# MAIN.net
KiCad netlist of a schematic drawn in Altium Designer
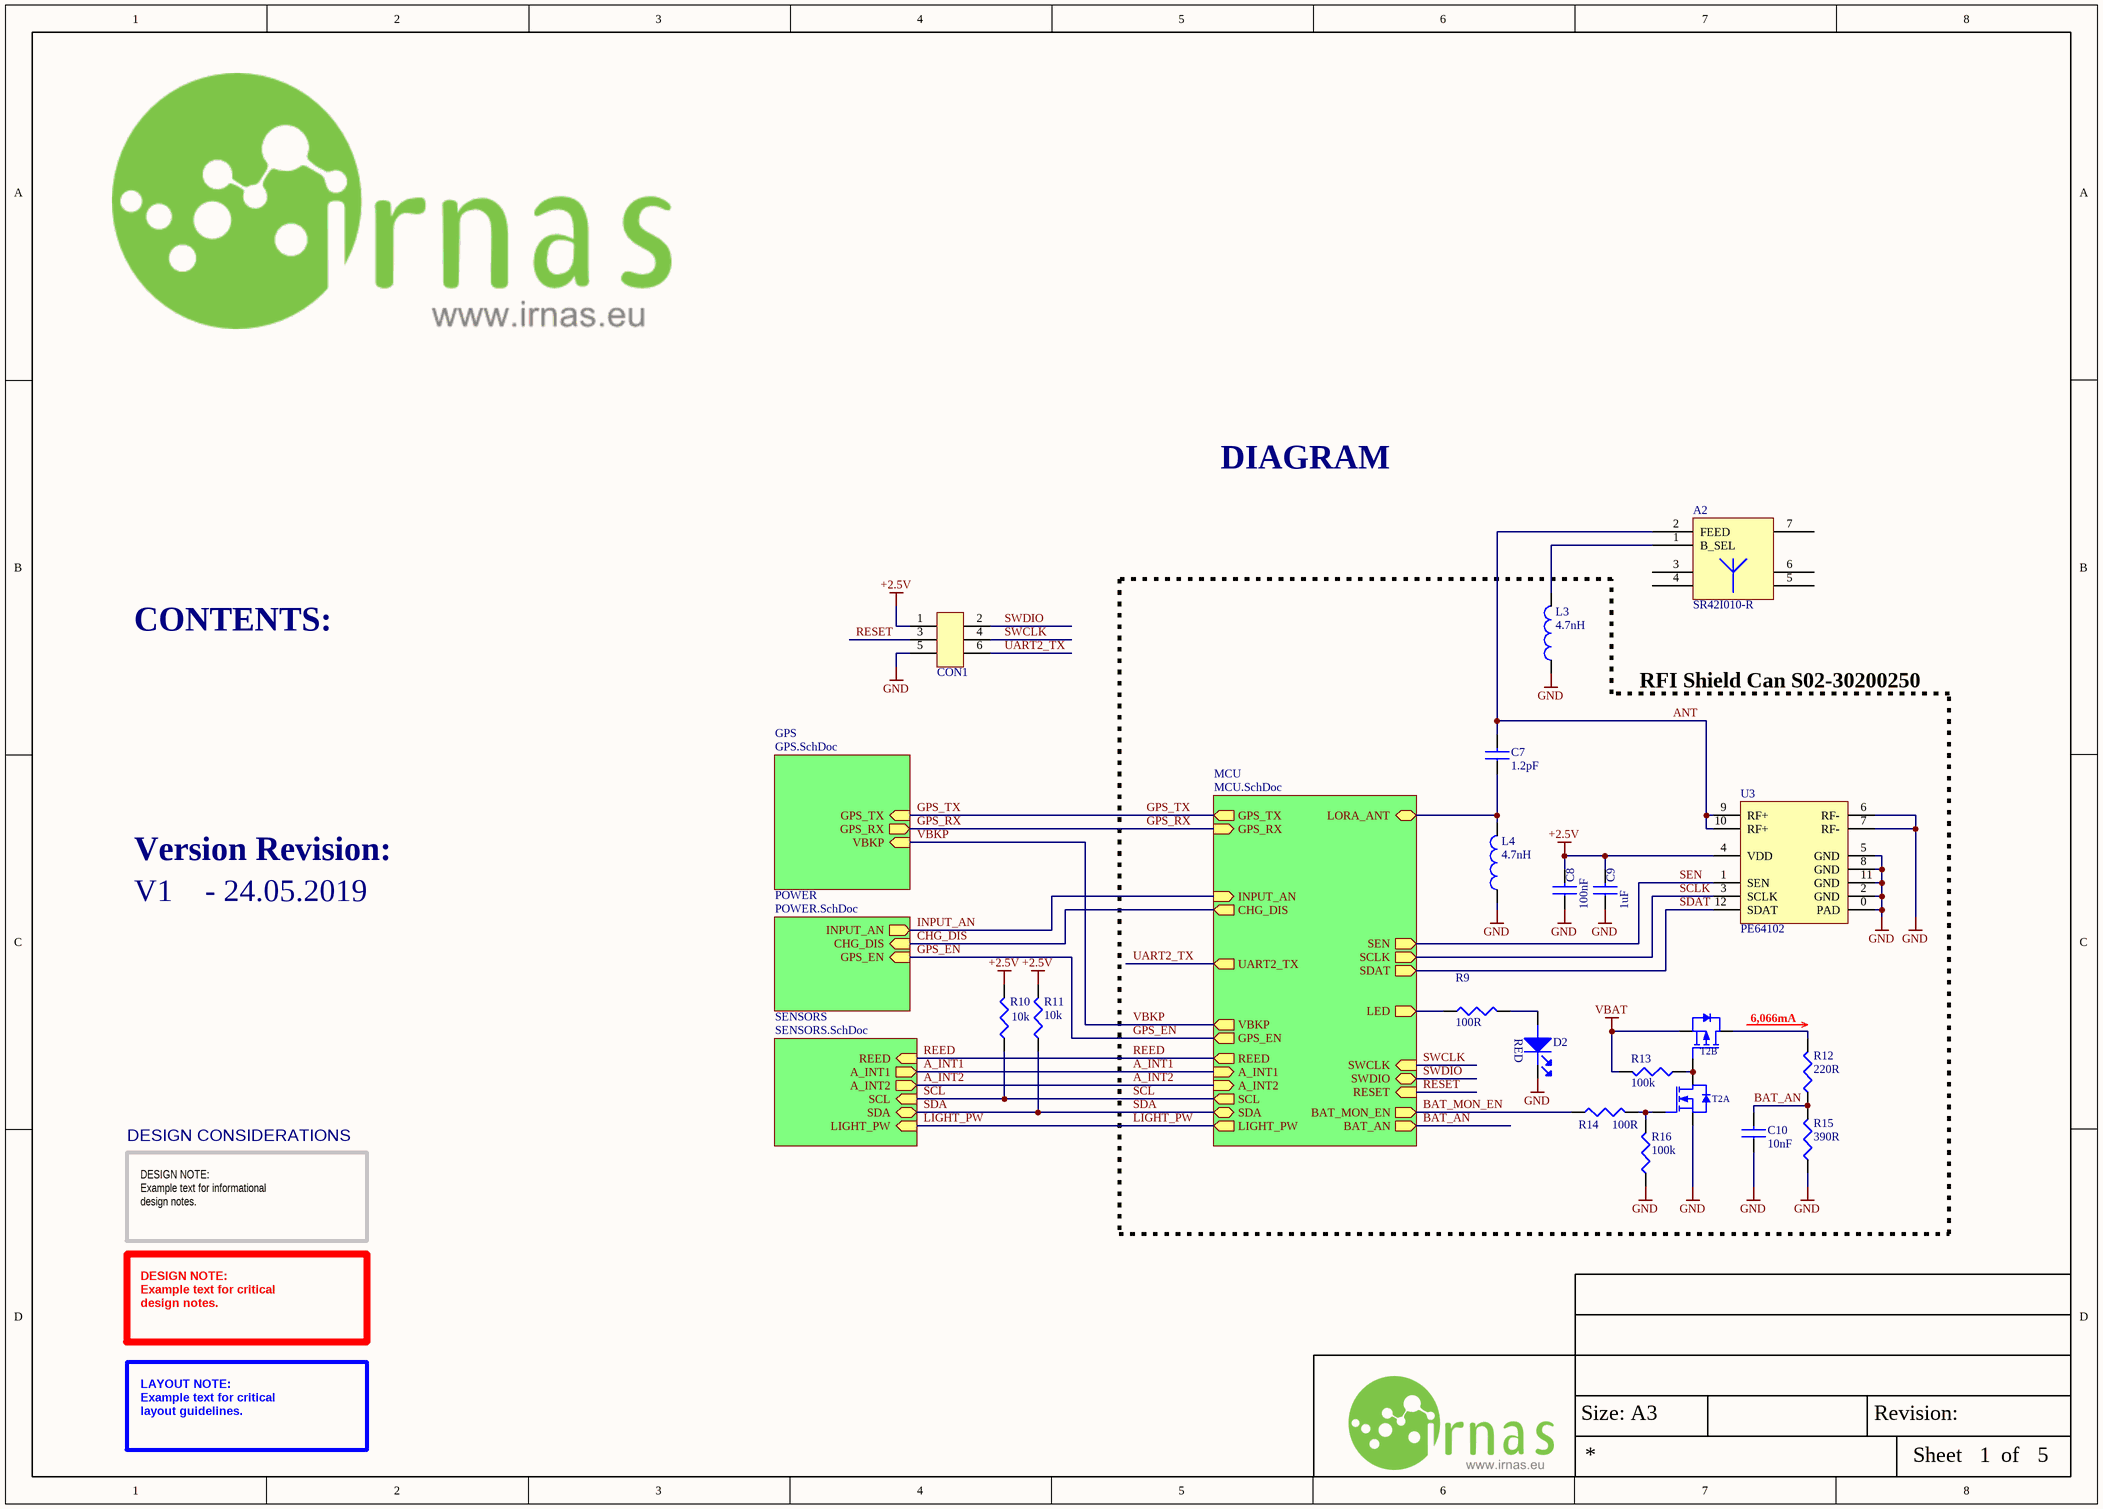
[diagram p0: MAIN.SchDoc]

(export (version "E")
  (design (tool "Eeschema 10.0.6"))
  (components
    (comp (ref "A2")
      (value "SR42I010-R")
      (footprint "LORA_PCB_ANTENNA")
      (description "Antenna SMD -4dBi Gain 870MHz/928MHz Automotive 7-Pin SMD T/R")
      (fields (field (name "MANUFACTURER") "Antenova"))
      (libsource (lib "Passive") (part "ANT - SR42I010-R_1"))
    )
    (comp (ref "C7")
      (value "1.2pF")
      (footprint "CAP0402")
      (description "CAP CER 4700PF 50V X7R 0402")
      (fields
        (field (name "MANUFACTURER") "KEMET")
        (field (name "MANUFACTURER PART NUMBER") "C0402C472K5RAC-TU")
      )
      (libsource (lib "Passive") (part "C - 4.7nF/0402"))
    )
    (comp (ref "C8")
      (value "100nF")
      (footprint "CAP0402")
      (fields
        (field (name "MANUFACTURER") "Multicomp")
        (field (name "MANUFACTURER PART NUMBER") "MC0402X104J160CT")
        (field (name "TOLERANCE") "5%")
      )
      (libsource (lib "Passive") (part "C - 100nF/0402"))
    )
    (comp (ref "C9")
      (value "1uF")
      (footprint "CAP0402")
      (description "CAP CER 1UF 10V 20% X5R 0402")
      (fields
        (field (name "MANUFACTURER") "Murata")
        (field (name "MANUFACTURER PART NUMBER") "GRM155R61A105ME15D")
      )
      (libsource (lib "Passive") (part "C - 1uF/0402"))
    )
    (comp (ref "C10")
      (value "10nF")
      (footprint "CAP0402")
      (description "CAP CER 10000PF 16V X7R 0402")
      (fields
        (field (name "MANUFACTURER") "Murata")
        (field (name "MANUFACTURER PART NUMBER") "GRM155R71C103KA01D")
      )
      (libsource (lib "Passive") (part "C - 10nF/0402"))
    )
    (comp (ref "CON1")
      (value "Tag connect")
      (footprint "TC2030-IDC-NL")
      (libsource (lib "Connectors") (part "tag connecot 6 pin"))
    )
    (comp (ref "D2")
      (value "LED RED")
      (footprint "LED0603")
      (description "BROADCOM LIMITED - HSMS-C190 - LED, RED, 10MCD, 626NM")
      (fields
        (field (name "MANUFACTURER") "BROADCOM LIMITED")
        (field (name "MANUFACTURER PART NUMBER") "HSMS-C190")
      )
      (libsource (lib "Active") (part "LED - LED RED"))
    )
    (comp (ref "L3")
      (value "4.7nH")
      (footprint "IND0402")
      (description "Inductor RF Chip Multi-Layer 4.3nH 0.3nH 100MHz 8Q-Factor Air 300mA 210mOhm DCR 0402 Paper T/R")
      (fields
        (field (name "MANUFACTURER") "Murata")
        (field (name "MANUFACTURER PART NUMBER") "LQG15HN4N3S02D")
      )
      (libsource (lib "Passive") (part "L - 4.3nH/0402"))
    )
    (comp (ref "L4")
      (value "4.7nH")
      (footprint "IND0402")
      (description "Inductor RF Chip Multi-Layer 4.3nH 0.3nH 100MHz 8Q-Factor Air 300mA 210mOhm DCR 0402 Paper T/R")
      (fields
        (field (name "MANUFACTURER") "Murata")
        (field (name "MANUFACTURER PART NUMBER") "LQG15HN4N3S02D")
      )
      (libsource (lib "Passive") (part "L - 4.3nH/0402"))
    )
    (comp (ref "R9")
      (value "100R")
      (footprint "RES0402")
      (fields
        (field (name "MANUFACTURER") "Multicomp")
        (field (name "MANUFACTURER PART NUMBER") "MCMR04X1000FTL")
        (field (name "TOLERANCE") "1%")
      )
      (libsource (lib "Passive") (part "R - 100R/0402"))
    )
    (comp (ref "R10")
      (value "10k")
      (footprint "RES0402")
      (fields
        (field (name "MANUFACTURER") "Multicomp")
        (field (name "MANUFACTURER PART NUMBER") "MCWR04X1002FTL")
        (field (name "TOLERANCE") "1%")
      )
      (libsource (lib "Passive") (part "R - 10k/0402"))
    )
    (comp (ref "R11")
      (value "10k")
      (footprint "RES0402")
      (fields
        (field (name "MANUFACTURER") "Multicomp")
        (field (name "MANUFACTURER PART NUMBER") "MCWR04X1002FTL")
        (field (name "TOLERANCE") "1%")
      )
      (libsource (lib "Passive") (part "R - 10k/0402"))
    )
    (comp (ref "R12")
      (value "220R")
      (footprint "RES0402")
      (description "SMD Chip Resistor, 0402 [1005 Metric], 220 ohm, CRCW e3 Series, 50 V, Thick Film, 63 mW")
      (fields (field (name "MANUFACTURER") "Multicomp") (field (name "IRNAS PART NO.") "/"))
      (libsource (lib "Passive") (part "R - 220R/0402"))
    )
    (comp (ref "R13")
      (value "100k")
      (footprint "RES0402")
      (description "MULTICOMP   MCWR04X1003FTL   RES, THICK FILM, 100KOHM, 1%, 0.0625W")
      (fields
        (field (name "MANUFACTURER") "Multicomp")
        (field (name "MANUFACTURER PART NUMBER") "MCWR04X1003FTL")
      )
      (libsource (lib "Passive") (part "R - 100k/0402"))
    )
    (comp (ref "R14")
      (value "100R")
      (footprint "RES0402")
      (fields
        (field (name "MANUFACTURER") "Multicomp")
        (field (name "MANUFACTURER PART NUMBER") "MCMR04X1000FTL")
        (field (name "TOLERANCE") "1%")
      )
      (libsource (lib "Passive") (part "R - 100R/0402"))
    )
    (comp (ref "R15")
      (value "390R")
      (footprint "RES0402")
      (description "SMD Chip Resistor, 0402 [1005 Metric], 390 ohm, MCWR Series, 50 V, Thick Film, 62.5 mW")
      (fields (field (name "MANUFACTURER") "Multicomp") (field (name "IRNAS PART NO.") "/"))
      (libsource (lib "Passive") (part "R - 390R/0402"))
    )
    (comp (ref "R16")
      (value "100k")
      (footprint "RES0402")
      (description "MULTICOMP   MCWR04X1003FTL   RES, THICK FILM, 100KOHM, 1%, 0.0625W")
      (fields
        (field (name "MANUFACTURER") "Multicomp")
        (field (name "MANUFACTURER PART NUMBER") "MCWR04X1003FTL")
      )
      (libsource (lib "Passive") (part "R - 100k/0402"))
    )
    (comp (ref "T2")
      (value "VT6M1T2CR")
      (footprint "VMT6")
      (description "Dual MOSFET, N and P Channel, 100 mA, 20 V, 2.5 ohm, 4.5 V, 1 V")
      (fields (field (name "AUTHOR") "Ciril Golob"))
      (libsource (lib "Active") (part "T_M - VT6M1T2CR"))
    )
    (comp (ref "U3")
      (value "PE64102")
      (footprint "QFN-12")
      (description "RF IC Digitally Tunable Capacitor General Purpose 100MHz ~ 3GHz SPI Interface 12-QFN (2x2)")
      (fields (field (name "MANUFACTURER") "u-blox") (field (name "MANUFACTURER PART NUMBER") "MAX-M8Q-0"))
      (libsource (lib "Active") (part "RF - PE64102"))
    )
  )
  (nets
    (net (code "1") (name "+2.5V") (class "Default")
      (node (ref "C8") (pin "2") (pinfunction "2_2") (pintype "passive"))
      (node (ref "C9") (pin "2") (pinfunction "2_2") (pintype "passive"))
      (node (ref "CON1") (pin "1") (pinfunction "1_1") (pintype "open_collector"))
      (node (ref "R10") (pin "2") (pinfunction "2_2") (pintype "passive"))
      (node (ref "R11") (pin "2") (pinfunction "2_2") (pintype "passive"))
      (node (ref "U3") (pin "4") (pinfunction "VDD_4") (pintype "passive"))
    )
    (net (code "2") (name "/ANT") (class "Default")
      (node (ref "A2") (pin "2") (pinfunction "FEED_2") (pintype "passive"))
      (node (ref "C7") (pin "2") (pinfunction "2_2") (pintype "passive"))
      (node (ref "U3") (pin "10") (pinfunction "RF+_10") (pintype "passive"))
      (node (ref "U3") (pin "9") (pinfunction "RF+_9") (pintype "passive"))
    )
    (net (code "5") (name "/BAT_AN") (class "Default")
      (node (ref "C10") (pin "2") (pinfunction "2_2") (pintype "passive"))
      (node (ref "R12") (pin "1") (pinfunction "1_1") (pintype "passive"))
      (node (ref "R15") (pin "2") (pinfunction "2_2") (pintype "passive"))
    )
    (net (code "6") (name "/BAT_MON_EN") (class "Default")
      (node (ref "R14") (pin "1") (pinfunction "1_1") (pintype "passive"))
    )
    (net (code "12") (name "/LED") (class "Default")
      (node (ref "R9") (pin "1") (pinfunction "1_1") (pintype "passive"))
    )
    (net (code "14") (name "/LORA_ANT") (class "Default")
      (node (ref "C7") (pin "1") (pinfunction "1_1") (pintype "passive"))
      (node (ref "L4") (pin "2") (pinfunction "2_2") (pintype "passive"))
    )
    (net (code "16") (name "/RESET") (class "Default")
      (node (ref "CON1") (pin "3") (pinfunction "3_3") (pintype "open_collector"))
    )
    (net (code "17") (name "/SCL") (class "Default")
      (node (ref "R10") (pin "1") (pinfunction "1_1") (pintype "passive"))
    )
    (net (code "18") (name "/SCLK") (class "Default")
      (node (ref "U3") (pin "3") (pinfunction "SCLK_3") (pintype "passive"))
    )
    (net (code "19") (name "/SDA") (class "Default")
      (node (ref "R11") (pin "1") (pinfunction "1_1") (pintype "passive"))
    )
    (net (code "20") (name "/SDAT") (class "Default")
      (node (ref "U3") (pin "12") (pinfunction "SDAT_12") (pintype "passive"))
    )
    (net (code "21") (name "/SEN") (class "Default")
      (node (ref "U3") (pin "1") (pinfunction "SEN_1") (pintype "passive"))
    )
    (net (code "22") (name "/SWCLK") (class "Default")
      (node (ref "CON1") (pin "4") (pinfunction "4_4") (pintype "open_collector"))
    )
    (net (code "23") (name "/SWDIO") (class "Default")
      (node (ref "CON1") (pin "2") (pinfunction "2_2") (pintype "open_collector"))
    )
    (net (code "24") (name "/UART2_TX") (class "Default")
      (node (ref "CON1") (pin "6") (pinfunction "6_6") (pintype "passive"))
    )
    (net (code "26") (name "GND") (class "Default")
      (node (ref "C10") (pin "1") (pinfunction "1_1") (pintype "passive"))
      (node (ref "C8") (pin "1") (pinfunction "1_1") (pintype "passive"))
      (node (ref "C9") (pin "1") (pinfunction "1_1") (pintype "passive"))
      (node (ref "CON1") (pin "5") (pinfunction "5_5") (pintype "open_collector"))
      (node (ref "D2") (pin "1") (pinfunction "cathode_1") (pintype "passive"))
      (node (ref "L3") (pin "1") (pinfunction "1_1") (pintype "passive"))
      (node (ref "L4") (pin "1") (pinfunction "1_1") (pintype "passive"))
      (node (ref "R15") (pin "1") (pinfunction "1_1") (pintype "passive"))
      (node (ref "R16") (pin "1") (pinfunction "1_1") (pintype "passive"))
      (node (ref "T2") (pin "1") (pinfunction "S1_1") (pintype "passive"))
      (node (ref "U3") (pin "0") (pinfunction "PAD_0") (pintype "passive"))
      (node (ref "U3") (pin "11") (pinfunction "GND_11") (pintype "passive"))
      (node (ref "U3") (pin "2") (pinfunction "GND_2") (pintype "passive"))
      (node (ref "U3") (pin "5") (pinfunction "GND_5") (pintype "passive"))
      (node (ref "U3") (pin "6") (pinfunction "RF-_6") (pintype "passive"))
      (node (ref "U3") (pin "7") (pinfunction "RF-_7") (pintype "passive"))
      (node (ref "U3") (pin "8") (pinfunction "GND_8") (pintype "passive"))
    )
    (net (code "27") (name "Net-(A2-B_SEL)") (class "Default")
      (node (ref "A2") (pin "1") (pinfunction "B_SEL_1") (pintype "passive"))
      (node (ref "L3") (pin "2") (pinfunction "2_2") (pintype "passive"))
    )
    (net (code "28") (name "Net-(D2-ANODE)") (class "Default")
      (node (ref "D2") (pin "2") (pinfunction "ANODE_2") (pintype "passive"))
      (node (ref "R9") (pin "2") (pinfunction "2_2") (pintype "passive"))
    )
    (net (code "29") (name "Net-(T2A-D1)") (class "Default")
      (node (ref "R13") (pin "1") (pinfunction "1_1") (pintype "passive"))
      (node (ref "T2") (pin "5") (pinfunction "G2_5") (pintype "passive"))
      (node (ref "T2") (pin "6") (pinfunction "D1_6") (pintype "passive"))
    )
    (net (code "30") (name "Net-(T2A-G1)") (class "Default")
      (node (ref "R14") (pin "2") (pinfunction "2_2") (pintype "passive"))
      (node (ref "R16") (pin "2") (pinfunction "2_2") (pintype "passive"))
      (node (ref "T2") (pin "2") (pinfunction "G1_2") (pintype "passive"))
    )
    (net (code "31") (name "Net-(T2B-D2)") (class "Default")
      (node (ref "R12") (pin "2") (pinfunction "2_2") (pintype "passive"))
      (node (ref "T2") (pin "3") (pinfunction "D2_3") (pintype "passive"))
    )
    (net (code "32") (name "VBAT") (class "Default")
      (node (ref "R13") (pin "2") (pinfunction "2_2") (pintype "passive"))
      (node (ref "T2") (pin "4") (pinfunction "S2_4") (pintype "passive"))
    )
    (net (code "33") (name "unconnected-(A2-Pad3)") (class "Default")
      (node (ref "A2") (pin "3") (pintype "passive"))
    )
    (net (code "34") (name "unconnected-(A2-Pad4)") (class "Default")
      (node (ref "A2") (pin "4") (pintype "passive"))
    )
    (net (code "35") (name "unconnected-(A2-Pad5)") (class "Default")
      (node (ref "A2") (pin "5") (pintype "passive"))
    )
    (net (code "36") (name "unconnected-(A2-Pad6)") (class "Default")
      (node (ref "A2") (pin "6") (pintype "passive"))
    )
    (net (code "37") (name "unconnected-(A2-Pad7)") (class "Default")
      (node (ref "A2") (pin "7") (pintype "passive"))
    )
  )
)
